# adapter.net
KiCad netlist of a schematic drawn in EAGLE
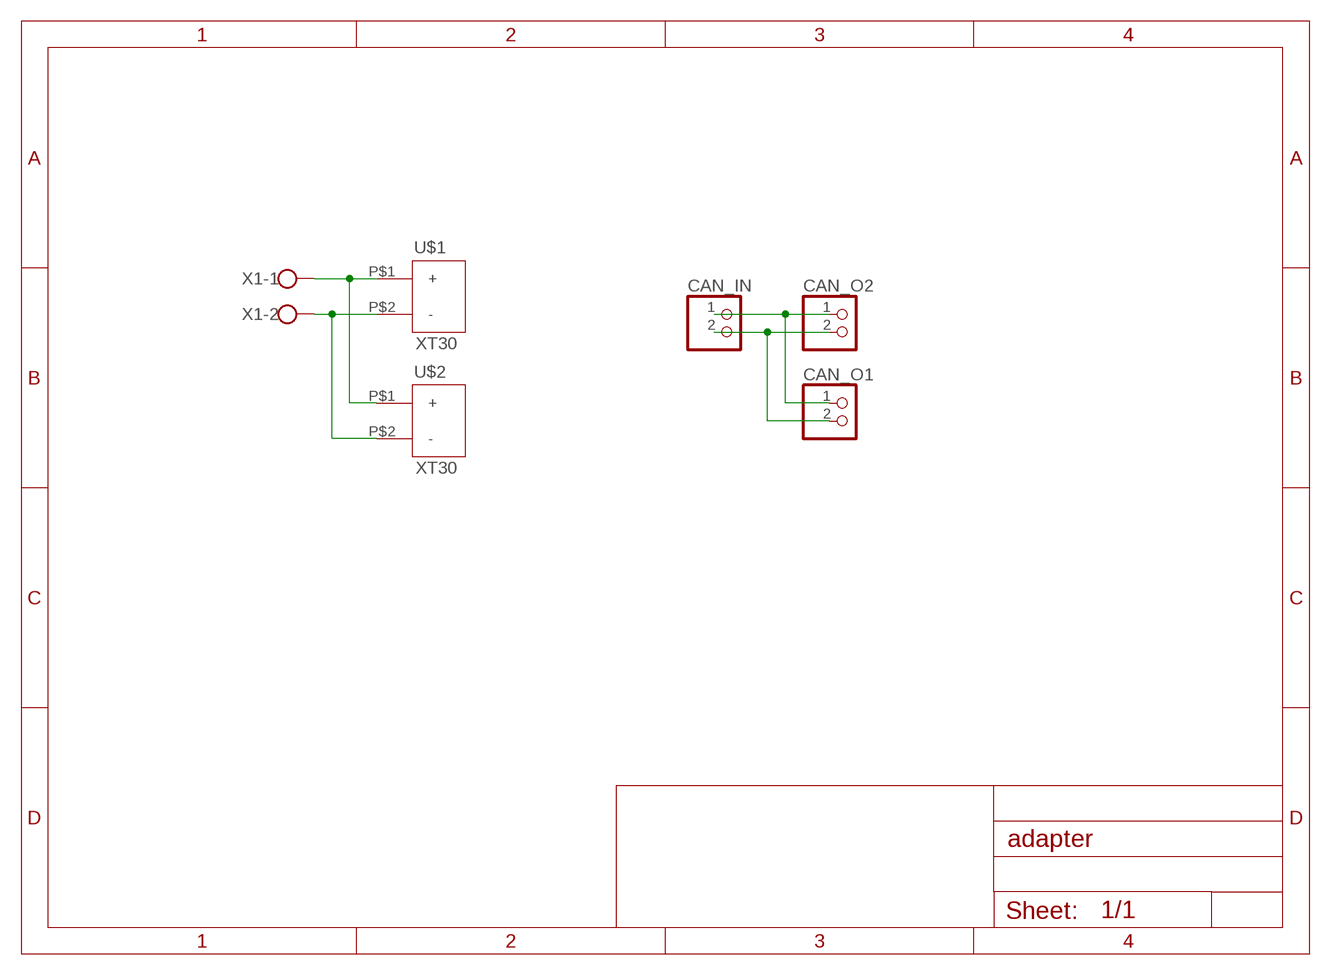
[diagram p0: schematic, sheet 1]

(export (version "E")
  (design (tool "Eeschema 10.0.6"))
  (components
    (comp (ref "CAN_IN")
      (value "PINHD-1X2")
      (footprint "eagle-import:1X02")
      (libsource (lib "eagle-import") (part "PINHD-1X2"))
    )
    (comp (ref "CAN_O1")
      (value "PINHD-1X2")
      (footprint "eagle-import:1X02")
      (libsource (lib "eagle-import") (part "PINHD-1X2"))
    )
    (comp (ref "CAN_O2")
      (value "PINHD-1X2")
      (footprint "eagle-import:1X02")
      (libsource (lib "eagle-import") (part "PINHD-1X2"))
    )
    (comp (ref "U$1")
      (value "XT30")
      (footprint "eagle-import:XT30U-F")
      (libsource (lib "eagle-import") (part "XT30"))
    )
    (comp (ref "U$2")
      (value "XT30")
      (footprint "eagle-import:XT30U-F")
      (libsource (lib "eagle-import") (part "XT30"))
    )
    (comp (ref "X1")
      (value "W237-102")
      (footprint "eagle-import:W237-102")
      (fields (field (name "MPN") "237-102"))
      (libsource (lib "eagle-import") (part "W237-102"))
    )
  )
  (nets
    (net (code "1") (name "Net-(CAN_IN-Pad1)") (class "Default")
      (node (ref "CAN_IN") (pin "1") (pinfunction "1_1") (pintype "passive"))
      (node (ref "CAN_O1") (pin "1") (pinfunction "1_1") (pintype "passive"))
      (node (ref "CAN_O2") (pin "1") (pinfunction "1_1") (pintype "passive"))
    )
    (net (code "2") (name "Net-(CAN_IN-Pad2)") (class "Default")
      (node (ref "CAN_IN") (pin "2") (pinfunction "2_2") (pintype "passive"))
      (node (ref "CAN_O1") (pin "2") (pinfunction "2_2") (pintype "passive"))
      (node (ref "CAN_O2") (pin "2") (pinfunction "2_2") (pintype "passive"))
    )
    (net (code "3") (name "Net-(U$1-+)") (class "Default")
      (node (ref "U$1") (pin "P$1") (pinfunction "+_P$1") (pintype "bidirectional"))
      (node (ref "U$2") (pin "P$1") (pinfunction "+_P$1") (pintype "bidirectional"))
      (node (ref "X1") (pin "1") (pinfunction "KL_1") (pintype "passive"))
    )
    (net (code "4") (name "Net-(U$1--)") (class "Default")
      (node (ref "U$1") (pin "P$2") (pinfunction "-_P$2") (pintype "bidirectional"))
      (node (ref "U$2") (pin "P$2") (pinfunction "-_P$2") (pintype "bidirectional"))
      (node (ref "X1") (pin "2") (pinfunction "KL_2") (pintype "passive"))
    )
  )
)
